# EPROM-EMU.net
KiCad netlist of a schematic drawn in Altium Designer
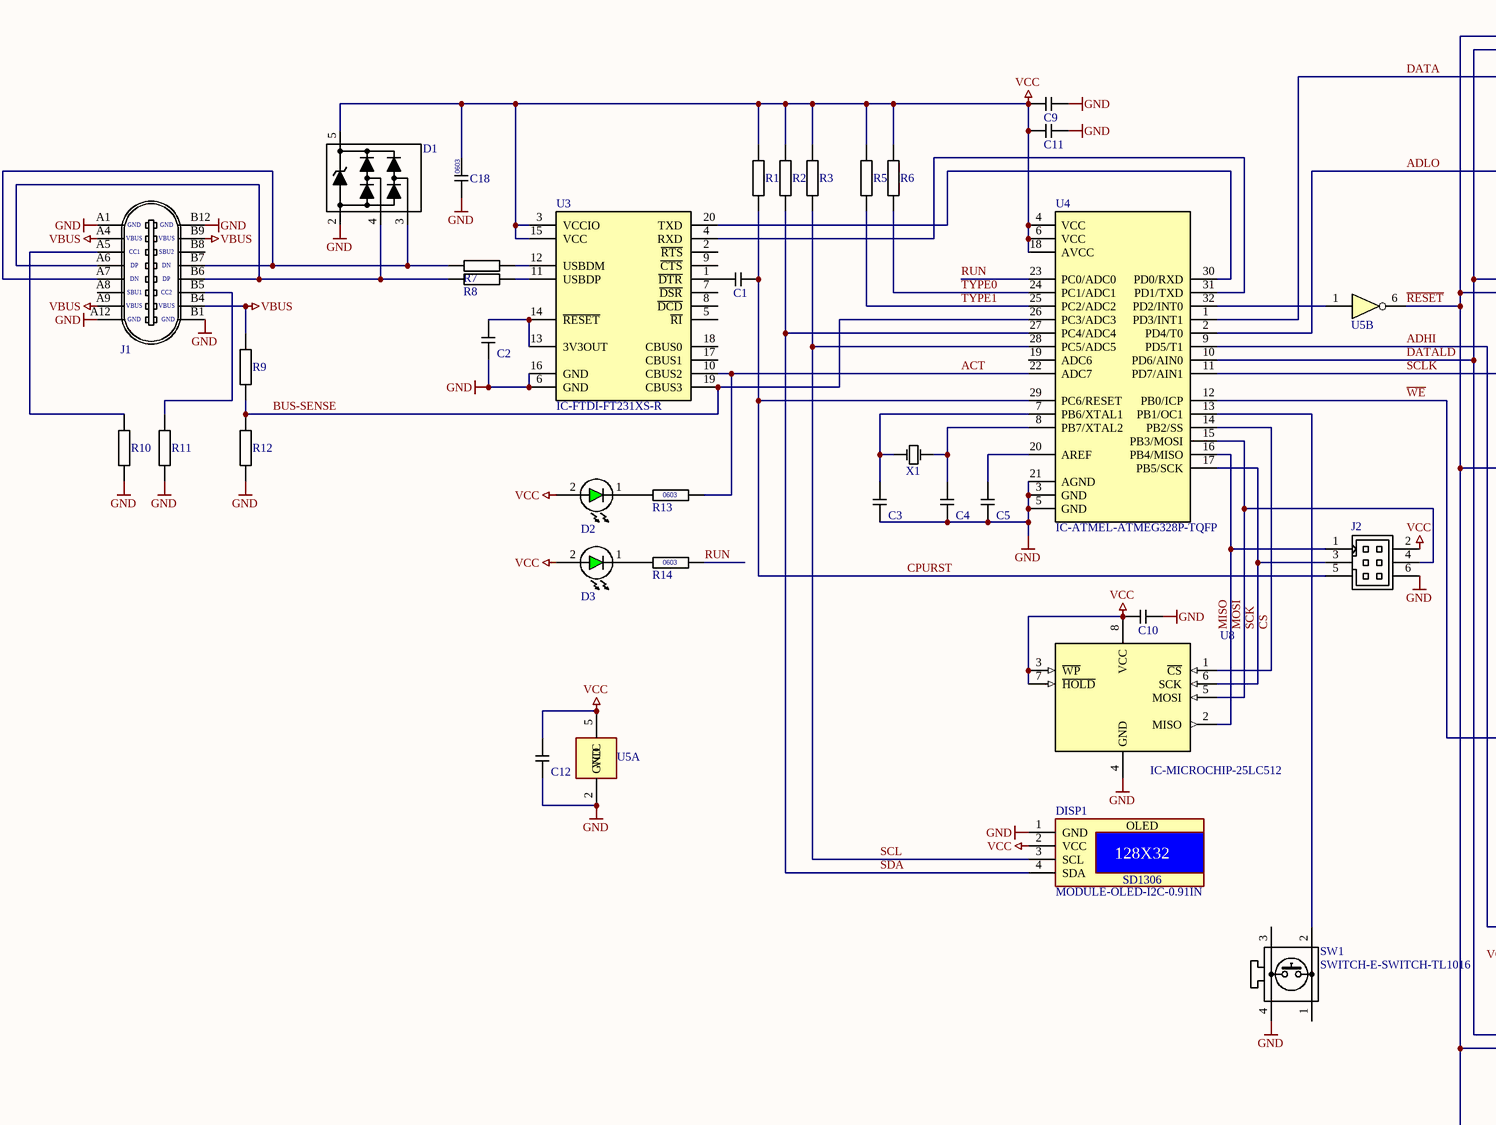
[diagram p0: EPROM-EMU.SchDoc, left]
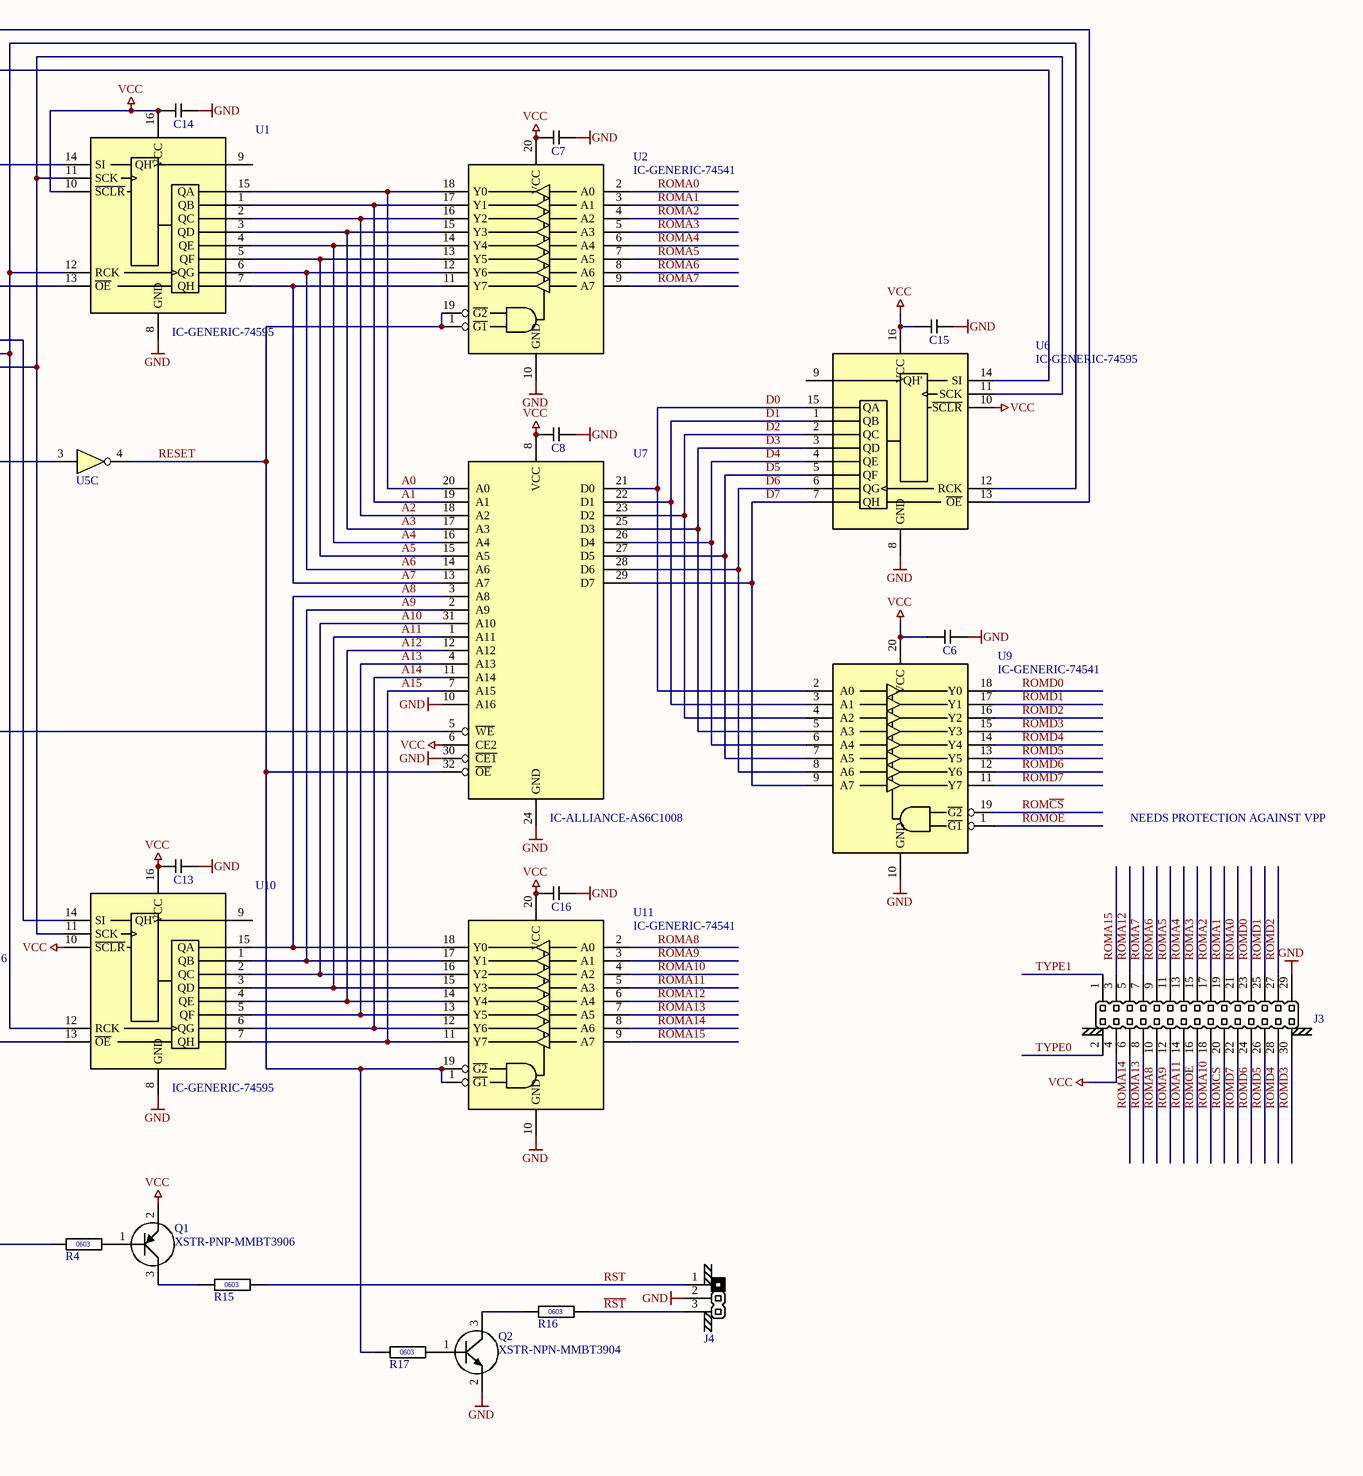
[diagram p1: EPROM-EMU.SchDoc, right]

(export (version "E")
  (design (tool "Eeschema 10.0.6"))
  (components
    (comp (ref "C1")
      (value "GENERIC-CAP")
      (footprint "CAP0603")
      (libsource (lib "eprom-emu") (part "GENERIC-CAP"))
    )
    (comp (ref "C2")
      (value "GENERIC-CAP")
      (footprint "CAP0603")
      (libsource (lib "eprom-emu") (part "GENERIC-CAP"))
    )
    (comp (ref "C3")
      (value "GENERIC-CAP")
      (footprint "CAP0603")
      (libsource (lib "eprom-emu") (part "GENERIC-CAP"))
    )
    (comp (ref "C4")
      (value "GENERIC-CAP")
      (footprint "CAP0603")
      (libsource (lib "eprom-emu") (part "GENERIC-CAP"))
    )
    (comp (ref "C5")
      (value "GENERIC-CAP")
      (footprint "CAP0603")
      (libsource (lib "eprom-emu") (part "GENERIC-CAP"))
    )
    (comp (ref "C6")
      (value "GENERIC-CAP")
      (footprint "CAP0603")
      (libsource (lib "eprom-emu") (part "GENERIC-CAP"))
    )
    (comp (ref "C7")
      (value "GENERIC-CAP")
      (footprint "CAP0603")
      (libsource (lib "eprom-emu") (part "GENERIC-CAP"))
    )
    (comp (ref "C8")
      (value "GENERIC-CAP")
      (footprint "CAP0603")
      (libsource (lib "eprom-emu") (part "GENERIC-CAP"))
    )
    (comp (ref "C9")
      (value "GENERIC-CAP")
      (footprint "CAP0603")
      (libsource (lib "eprom-emu") (part "GENERIC-CAP"))
    )
    (comp (ref "C10")
      (value "GENERIC-CAP")
      (footprint "CAP0603")
      (libsource (lib "eprom-emu") (part "GENERIC-CAP"))
    )
    (comp (ref "C11")
      (value "GENERIC-CAP")
      (footprint "CAP0603")
      (libsource (lib "eprom-emu") (part "GENERIC-CAP"))
    )
    (comp (ref "C12")
      (value "GENERIC-CAP")
      (footprint "CAP0603")
      (libsource (lib "eprom-emu") (part "GENERIC-CAP"))
    )
    (comp (ref "C13")
      (value "GENERIC-CAP")
      (footprint "CAP0603")
      (libsource (lib "eprom-emu") (part "GENERIC-CAP"))
    )
    (comp (ref "C14")
      (value "GENERIC-CAP")
      (footprint "CAP0603")
      (libsource (lib "eprom-emu") (part "GENERIC-CAP"))
    )
    (comp (ref "C15")
      (value "GENERIC-CAP")
      (footprint "CAP0603")
      (libsource (lib "eprom-emu") (part "GENERIC-CAP"))
    )
    (comp (ref "C16")
      (value "GENERIC-CAP")
      (footprint "CAP0603")
      (libsource (lib "eprom-emu") (part "GENERIC-CAP"))
    )
    (comp (ref "C18")
      (value "GENERIC-CAP-0603")
      (footprint "CAP0603")
      (libsource (lib "eprom-emu") (part "GENERIC-CAP-0603"))
    )
    (comp (ref "D1")
      (value "TVS-WURTH-824011")
      (footprint "SOT23-5")
      (libsource (lib "eprom-emu") (part "TVS-WURTH-824011"))
    )
    (comp (ref "D2")
      (value "LED-PLCC2-GREEN")
      (footprint "LED-PLCC2-GREEN")
      (libsource (lib "eprom-emu") (part "LED-PLCC2-GREEN"))
    )
    (comp (ref "D3")
      (value "LED-PLCC2-GREEN")
      (footprint "LED-PLCC2-GREEN")
      (libsource (lib "eprom-emu") (part "LED-PLCC2-GREEN"))
    )
    (comp (ref "DISP1")
      (value "MODULE-OLED-I2C-0.91IN")
      (footprint "DISP-OLED-128X32")
      (libsource (lib "eprom-emu") (part "MODULE-OLED-I2C-0.91IN"))
    )
    (comp (ref "J1")
      (value "CUNN-USBC-USB2-VERT")
      (footprint "CONN-GCT-USB4085")
      (libsource (lib "eprom-emu") (part "CUNN-USBC-USB2-VERT"))
    )
    (comp (ref "J2")
      (value "BOXHEADER-3X2")
      (footprint "HEADER-2X3-1.27")
      (libsource (lib "eprom-emu") (part "CONN-BOXHEADER-3X2"))
    )
    (comp (ref "J3")
      (value "CONN-HEADER-RA-PIN-15X2")
      (footprint "HEADER-2X15-RA")
      (libsource (lib "eprom-emu") (part "CONN-HEADER-RA-PIN-15X2"))
    )
    (comp (ref "J4")
      (value "CONN-HEADER-PIN-1X3-254-RA")
      (footprint "HEADER-1X3-245-RA")
      (libsource (lib "eprom-emu") (part "CONN-HEADER-PIN-1X3-254-RA"))
    )
    (comp (ref "Q1")
      (value "XSTR-PNP-MMBT3906")
      (footprint "SOT23")
      (libsource (lib "eprom-emu") (part "XSTR-PNP-MMBT3906"))
    )
    (comp (ref "Q2")
      (value "XSTR-NPN-MMBT3904")
      (footprint "SOT23")
      (libsource (lib "eprom-emu") (part "XSTR-NPN-MMBT3904"))
    )
    (comp (ref "R1")
      (value "GENERIC-RES")
      (footprint "RES0603")
      (libsource (lib "eprom-emu") (part "GENERIC-RES"))
    )
    (comp (ref "R2")
      (value "GENERIC-RES")
      (footprint "RES0603")
      (libsource (lib "eprom-emu") (part "GENERIC-RES"))
    )
    (comp (ref "R3")
      (value "GENERIC-RES")
      (footprint "RES0603")
      (libsource (lib "eprom-emu") (part "GENERIC-RES"))
    )
    (comp (ref "R4")
      (value "GENERIC-RES-0603")
      (footprint "RES0603")
      (libsource (lib "eprom-emu") (part "GENERIC-RES-0603"))
    )
    (comp (ref "R5")
      (value "GENERIC-RES")
      (footprint "RES0603")
      (libsource (lib "eprom-emu") (part "GENERIC-RES"))
    )
    (comp (ref "R6")
      (value "GENERIC-RES")
      (footprint "RES0603")
      (libsource (lib "eprom-emu") (part "GENERIC-RES"))
    )
    (comp (ref "R7")
      (value "GENERIC-RES")
      (footprint "RES0603")
      (libsource (lib "eprom-emu") (part "GENERIC-RES"))
    )
    (comp (ref "R8")
      (value "GENERIC-RES")
      (footprint "RES0603")
      (libsource (lib "eprom-emu") (part "GENERIC-RES"))
    )
    (comp (ref "R9")
      (value "GENERIC-RES")
      (footprint "RES0603")
      (libsource (lib "eprom-emu") (part "GENERIC-RES"))
    )
    (comp (ref "R10")
      (value "GENERIC-RES")
      (footprint "RES0603")
      (libsource (lib "eprom-emu") (part "GENERIC-RES"))
    )
    (comp (ref "R11")
      (value "GENERIC-RES")
      (footprint "RES0603")
      (libsource (lib "eprom-emu") (part "GENERIC-RES"))
    )
    (comp (ref "R12")
      (value "GENERIC-RES")
      (footprint "RES0603")
      (libsource (lib "eprom-emu") (part "GENERIC-RES"))
    )
    (comp (ref "R13")
      (value "GENERIC-RES-0603")
      (footprint "RES0603")
      (libsource (lib "eprom-emu") (part "GENERIC-RES-0603"))
    )
    (comp (ref "R14")
      (value "GENERIC-RES-0603")
      (footprint "RES0603")
      (libsource (lib "eprom-emu") (part "GENERIC-RES-0603"))
    )
    (comp (ref "R15")
      (value "GENERIC-RES-0603")
      (footprint "RES0603")
      (libsource (lib "eprom-emu") (part "GENERIC-RES-0603"))
    )
    (comp (ref "R16")
      (value "GENERIC-RES-0603")
      (footprint "RES0603")
      (libsource (lib "eprom-emu") (part "GENERIC-RES-0603"))
    )
    (comp (ref "R17")
      (value "GENERIC-RES-0603")
      (footprint "RES0603")
      (libsource (lib "eprom-emu") (part "GENERIC-RES-0603"))
    )
    (comp (ref "SW1")
      (value "SWITCH-E-SWITCH-TL1016")
      (footprint "SWITCH-ESWITCH-TL1016")
      (libsource (lib "eprom-emu") (part "SWITCH-E-SWITCH-TL1016"))
    )
    (comp (ref "U1")
      (value "IC-GENERIC-74595")
      (footprint "SO65P640X120-16N")
      (libsource (lib "eprom-emu") (part "IC-GENERIC-74595"))
    )
    (comp (ref "U2")
      (value "IC-GENERIC-74541")
      (footprint "SO65P640X110-20N")
      (libsource (lib "eprom-emu") (part "IC-GENERIC-74541"))
    )
    (comp (ref "U3")
      (value "IC-FTDI-FT231XS-R")
      (footprint "TSOP65P640-20N")
      (libsource (lib "eprom-emu") (part "IC-FTDI-FT231XS-R"))
    )
    (comp (ref "U4")
      (value "IC-ATMEL-ATMEG328P-TQFP")
      (footprint "QFP80P900X900-32N")
      (libsource (lib "eprom-emu") (part "IC-ATMEL-ATMEG328P-TQFP"))
    )
    (comp (ref "U5")
      (value "IC-TI-SN74LVC2G14")
      (footprint "SOT23-6")
      (description "IC-GENERIC-7408IC-TI-SN74LVC2G14")
      (libsource (lib "eprom-emu") (part "IC-TI-SN74LVC2G14"))
    )
    (comp (ref "U6")
      (value "IC-GENERIC-74595")
      (footprint "SO65P640X120-16N")
      (libsource (lib "") (part "IC-GENERIC-74595_1"))
    )
    (comp (ref "U7")
      (value "IC-ALLIANCE-AS6C1008")
      (footprint "TSSOP50P1340X125-32N")
      (libsource (lib "eprom-emu") (part "IC-ALLIANCE-AS6C1008"))
    )
    (comp (ref "U8")
      (value "IC-MICROCHIP-25LC512")
      (footprint "SO127P600-8N")
      (libsource (lib "eprom-emu") (part "IC-MICROCHIP-25LC512"))
    )
    (comp (ref "U9")
      (value "IC-GENERIC-74541")
      (footprint "SO65P640X110-20N")
      (libsource (lib "") (part "IC-GENERIC-74541_1"))
    )
    (comp (ref "U10")
      (value "IC-GENERIC-74595")
      (footprint "SO65P640X120-16N")
      (libsource (lib "eprom-emu") (part "IC-GENERIC-74595"))
    )
    (comp (ref "U11")
      (value "IC-GENERIC-74541")
      (footprint "SO65P640X110-20N")
      (libsource (lib "eprom-emu") (part "IC-GENERIC-74541"))
    )
    (comp (ref "X1")
      (value "CRYSTAL-2PIN")
      (footprint "XTAL-ABRACON-ABM3")
      (description "CRYSTAL 2 PIN GENERIC")
      (libsource (lib "eprom-emu") (part "CRYSTAL-2PIN"))
    )
  )
  (nets
    (net (code "1") (name "/A0") (class "Default")
      (node (ref "U1") (pin "15") (pinfunction "QA_15") (pintype "power_in"))
      (node (ref "U2") (pin "18") (pinfunction "Y0_18") (pintype "power_in"))
      (node (ref "U7") (pin "20") (pinfunction "A0_20") (pintype "passive"))
    )
    (net (code "2") (name "/A1") (class "Default")
      (node (ref "U1") (pin "1") (pinfunction "QB_1") (pintype "power_in"))
      (node (ref "U2") (pin "17") (pinfunction "Y1_17") (pintype "power_in"))
      (node (ref "U7") (pin "19") (pinfunction "A1_19") (pintype "passive"))
    )
    (net (code "3") (name "/A2") (class "Default")
      (node (ref "U1") (pin "2") (pinfunction "QC_2") (pintype "power_in"))
      (node (ref "U2") (pin "16") (pinfunction "Y2_16") (pintype "power_in"))
      (node (ref "U7") (pin "18") (pinfunction "A2_18") (pintype "passive"))
    )
    (net (code "4") (name "/A3") (class "Default")
      (node (ref "U1") (pin "3") (pinfunction "QD_3") (pintype "power_in"))
      (node (ref "U2") (pin "15") (pinfunction "Y3_15") (pintype "power_in"))
      (node (ref "U7") (pin "17") (pinfunction "A3_17") (pintype "passive"))
    )
    (net (code "5") (name "/A4") (class "Default")
      (node (ref "U1") (pin "4") (pinfunction "QE_4") (pintype "power_in"))
      (node (ref "U2") (pin "14") (pinfunction "Y4_14") (pintype "power_in"))
      (node (ref "U7") (pin "16") (pinfunction "A4_16") (pintype "passive"))
    )
    (net (code "6") (name "/A5") (class "Default")
      (node (ref "U1") (pin "5") (pinfunction "QF_5") (pintype "power_in"))
      (node (ref "U2") (pin "13") (pinfunction "Y5_13") (pintype "power_in"))
      (node (ref "U7") (pin "15") (pinfunction "A5_15") (pintype "passive"))
    )
    (net (code "7") (name "/A6") (class "Default")
      (node (ref "U1") (pin "6") (pinfunction "QG_6") (pintype "power_in"))
      (node (ref "U2") (pin "12") (pinfunction "Y6_12") (pintype "power_in"))
      (node (ref "U7") (pin "14") (pinfunction "A6_14") (pintype "passive"))
    )
    (net (code "8") (name "/A7") (class "Default")
      (node (ref "U1") (pin "7") (pinfunction "QH_7") (pintype "power_in"))
      (node (ref "U2") (pin "11") (pinfunction "Y7_11") (pintype "power_in"))
      (node (ref "U7") (pin "13") (pinfunction "A7_13") (pintype "passive"))
    )
    (net (code "9") (name "/A8") (class "Default")
      (node (ref "U10") (pin "15") (pinfunction "QA_15") (pintype "power_in"))
      (node (ref "U11") (pin "18") (pinfunction "Y0_18") (pintype "power_in"))
      (node (ref "U7") (pin "3") (pinfunction "A8_3") (pintype "passive"))
    )
    (net (code "10") (name "/A9") (class "Default")
      (node (ref "U10") (pin "1") (pinfunction "QB_1") (pintype "power_in"))
      (node (ref "U11") (pin "17") (pinfunction "Y1_17") (pintype "power_in"))
      (node (ref "U7") (pin "2") (pinfunction "A9_2") (pintype "passive"))
    )
    (net (code "11") (name "/A10") (class "Default")
      (node (ref "U10") (pin "2") (pinfunction "QC_2") (pintype "power_in"))
      (node (ref "U11") (pin "16") (pinfunction "Y2_16") (pintype "power_in"))
      (node (ref "U7") (pin "31") (pinfunction "A10_31") (pintype "passive"))
    )
    (net (code "12") (name "/A11") (class "Default")
      (node (ref "U10") (pin "3") (pinfunction "QD_3") (pintype "power_in"))
      (node (ref "U11") (pin "15") (pinfunction "Y3_15") (pintype "power_in"))
      (node (ref "U7") (pin "1") (pinfunction "A11_1") (pintype "passive"))
    )
    (net (code "13") (name "/A12") (class "Default")
      (node (ref "U10") (pin "4") (pinfunction "QE_4") (pintype "power_in"))
      (node (ref "U11") (pin "14") (pinfunction "Y4_14") (pintype "power_in"))
      (node (ref "U7") (pin "12") (pinfunction "A12_12") (pintype "passive"))
    )
    (net (code "14") (name "/A13") (class "Default")
      (node (ref "U10") (pin "5") (pinfunction "QF_5") (pintype "power_in"))
      (node (ref "U11") (pin "13") (pinfunction "Y5_13") (pintype "power_in"))
      (node (ref "U7") (pin "4") (pinfunction "A13_4") (pintype "passive"))
    )
    (net (code "15") (name "/A14") (class "Default")
      (node (ref "U10") (pin "6") (pinfunction "QG_6") (pintype "power_in"))
      (node (ref "U11") (pin "12") (pinfunction "Y6_12") (pintype "power_in"))
      (node (ref "U7") (pin "11") (pinfunction "A14_11") (pintype "passive"))
    )
    (net (code "16") (name "/A15") (class "Default")
      (node (ref "U10") (pin "7") (pinfunction "QH_7") (pintype "power_in"))
      (node (ref "U11") (pin "11") (pinfunction "Y7_11") (pintype "power_in"))
      (node (ref "U7") (pin "7") (pinfunction "A15_7") (pintype "passive"))
    )
    (net (code "17") (name "/ACT") (class "Default")
      (node (ref "R13") (pin "1") (pinfunction "1_1") (pintype "passive"))
      (node (ref "U3") (pin "10") (pinfunction "CBUS2_10") (pintype "power_in"))
      (node (ref "U4") (pin "22") (pinfunction "ADC7_22") (pintype "passive"))
    )
    (net (code "18") (name "/ADHI") (class "Default")
      (node (ref "U10") (pin "14") (pinfunction "SI_14") (pintype "power_in"))
      (node (ref "U4") (pin "9") (pinfunction "PD5/T1_9") (pintype "passive"))
    )
    (net (code "19") (name "/ADLO") (class "Default")
      (node (ref "U1") (pin "14") (pinfunction "SI_14") (pintype "power_in"))
      (node (ref "U4") (pin "2") (pinfunction "PD4/T0_2") (pintype "passive"))
    )
    (net (code "20") (name "/BUS-SENSE") (class "Default")
      (node (ref "R12") (pin "1") (pinfunction "1_1") (pintype "passive"))
      (node (ref "R9") (pin "2") (pinfunction "2_2") (pintype "passive"))
      (node (ref "U3") (pin "19") (pinfunction "CBUS3_19") (pintype "power_in"))
      (node (ref "U4") (pin "26") (pinfunction "PC3/ADC3_26") (pintype "passive"))
    )
    (net (code "21") (name "/CPURST") (class "Default")
      (node (ref "C1") (pin "2") (pinfunction "2_2") (pintype "passive"))
      (node (ref "J2") (pin "5") (pinfunction "-_5") (pintype "passive"))
      (node (ref "R1") (pin "1") (pinfunction "1_1") (pintype "passive"))
      (node (ref "U4") (pin "29") (pinfunction "PC6/RESET_29") (pintype "passive"))
    )
    (net (code "22") (name "/D0") (class "Default")
      (node (ref "U6") (pin "15") (pinfunction "QA_15") (pintype "power_in"))
      (node (ref "U7") (pin "21") (pinfunction "D0_21") (pintype "power_in"))
      (node (ref "U9") (pin "2") (pinfunction "A0_2") (pintype "power_in"))
    )
    (net (code "23") (name "/D1") (class "Default")
      (node (ref "U6") (pin "1") (pinfunction "QB_1") (pintype "power_in"))
      (node (ref "U7") (pin "22") (pinfunction "D1_22") (pintype "power_in"))
      (node (ref "U9") (pin "3") (pinfunction "A1_3") (pintype "power_in"))
    )
    (net (code "24") (name "/D2") (class "Default")
      (node (ref "U6") (pin "2") (pinfunction "QC_2") (pintype "power_in"))
      (node (ref "U7") (pin "23") (pinfunction "D2_23") (pintype "power_in"))
      (node (ref "U9") (pin "4") (pinfunction "A2_4") (pintype "power_in"))
    )
    (net (code "25") (name "/D3") (class "Default")
      (node (ref "U6") (pin "3") (pinfunction "QD_3") (pintype "power_in"))
      (node (ref "U7") (pin "25") (pinfunction "D3_25") (pintype "power_in"))
      (node (ref "U9") (pin "5") (pinfunction "A3_5") (pintype "power_in"))
    )
    (net (code "26") (name "/D4") (class "Default")
      (node (ref "U6") (pin "4") (pinfunction "QE_4") (pintype "power_in"))
      (node (ref "U7") (pin "26") (pinfunction "D4_26") (pintype "power_in"))
      (node (ref "U9") (pin "6") (pinfunction "A4_6") (pintype "power_in"))
    )
    (net (code "27") (name "/D5") (class "Default")
      (node (ref "U6") (pin "5") (pinfunction "QF_5") (pintype "power_in"))
      (node (ref "U7") (pin "27") (pinfunction "D5_27") (pintype "power_in"))
      (node (ref "U9") (pin "7") (pinfunction "A5_7") (pintype "power_in"))
    )
    (net (code "28") (name "/D6") (class "Default")
      (node (ref "U6") (pin "6") (pinfunction "QG_6") (pintype "power_in"))
      (node (ref "U7") (pin "28") (pinfunction "D6_28") (pintype "power_in"))
      (node (ref "U9") (pin "8") (pinfunction "A6_8") (pintype "power_in"))
    )
    (net (code "29") (name "/D7") (class "Default")
      (node (ref "U6") (pin "7") (pinfunction "QH_7") (pintype "power_in"))
      (node (ref "U7") (pin "29") (pinfunction "D7_29") (pintype "power_in"))
      (node (ref "U9") (pin "9") (pinfunction "A7_9") (pintype "power_in"))
    )
    (net (code "30") (name "/DATA") (class "Default")
      (node (ref "U4") (pin "1") (pinfunction "PD3/INT1_1") (pintype "passive"))
      (node (ref "U6") (pin "14") (pinfunction "SI_14") (pintype "power_in"))
    )
    (net (code "31") (name "/DATALD") (class "Default")
      (node (ref "U1") (pin "12") (pinfunction "RCK_12") (pintype "power_in"))
      (node (ref "U10") (pin "12") (pinfunction "RCK_12") (pintype "power_in"))
      (node (ref "U4") (pin "10") (pinfunction "PD6/AIN0_10") (pintype "passive"))
      (node (ref "U6") (pin "12") (pinfunction "RCK_12") (pintype "power_in"))
    )
    (net (code "32") (name "/MISO") (class "Default")
      (node (ref "J2") (pin "1") (pinfunction "+_1") (pintype "passive"))
      (node (ref "U4") (pin "16") (pinfunction "PB4/MISO_16") (pintype "passive"))
      (node (ref "U8") (pin "2") (pinfunction "MISO_2") (pintype "output"))
    )
    (net (code "33") (name "/MOSI") (class "Default")
      (node (ref "J2") (pin "4") (pinfunction "-_4") (pintype "passive"))
      (node (ref "U4") (pin "15") (pinfunction "PB3/MOSI_15") (pintype "passive"))
      (node (ref "U8") (pin "5") (pinfunction "MOSI_5") (pintype "input"))
    )
    (net (code "34") (name "/RESET") (class "Default")
      (node (ref "R17") (pin "2") (pinfunction "2_2") (pintype "passive"))
      (node (ref "U11") (pin "1") (pinfunction "~{G1}_1") (pintype "power_in"))
      (node (ref "U11") (pin "19") (pinfunction "~{G2}_19") (pintype "power_in"))
      (node (ref "U2") (pin "1") (pinfunction "~{G1}_1") (pintype "power_in"))
      (node (ref "U2") (pin "19") (pinfunction "~{G2}_19") (pintype "power_in"))
      (node (ref "U5") (pin "4") (pinfunction "4_4") (pintype "passive"))
      (node (ref "U7") (pin "32") (pinfunction "~{OE}_32") (pintype "power_in"))
    )
    (net (code "35") (name "/ROMA0") (class "Default")
      (node (ref "J3") (pin "21") (pinfunction "-_21") (pintype "passive"))
      (node (ref "U2") (pin "2") (pinfunction "A0_2") (pintype "power_in"))
    )
    (net (code "36") (name "/ROMA1") (class "Default")
      (node (ref "J3") (pin "19") (pinfunction "+_19") (pintype "passive"))
      (node (ref "U2") (pin "3") (pinfunction "A1_3") (pintype "power_in"))
    )
    (net (code "37") (name "/ROMA2") (class "Default")
      (node (ref "J3") (pin "17") (pinfunction "-_17") (pintype "passive"))
      (node (ref "U2") (pin "4") (pinfunction "A2_4") (pintype "power_in"))
    )
    (net (code "38") (name "/ROMA3") (class "Default")
      (node (ref "J3") (pin "15") (pinfunction "-_15") (pintype "passive"))
      (node (ref "U2") (pin "5") (pinfunction "A3_5") (pintype "power_in"))
    )
    (net (code "39") (name "/ROMA4") (class "Default")
      (node (ref "J3") (pin "13") (pinfunction "+_13") (pintype "passive"))
      (node (ref "U2") (pin "6") (pinfunction "A4_6") (pintype "power_in"))
    )
    (net (code "40") (name "/ROMA5") (class "Default")
      (node (ref "J3") (pin "11") (pinfunction "-_11") (pintype "passive"))
      (node (ref "U2") (pin "7") (pinfunction "A5_7") (pintype "power_in"))
    )
    (net (code "41") (name "/ROMA6") (class "Default")
      (node (ref "J3") (pin "9") (pinfunction "-_9") (pintype "passive"))
      (node (ref "U2") (pin "8") (pinfunction "A6_8") (pintype "power_in"))
    )
    (net (code "42") (name "/ROMA7") (class "Default")
      (node (ref "J3") (pin "7") (pinfunction "+_7") (pintype "passive"))
      (node (ref "U2") (pin "9") (pinfunction "A7_9") (pintype "power_in"))
    )
    (net (code "43") (name "/ROMA8") (class "Default")
      (node (ref "J3") (pin "10") (pinfunction "-_10") (pintype "passive"))
      (node (ref "U11") (pin "2") (pinfunction "A0_2") (pintype "power_in"))
    )
    (net (code "44") (name "/ROMA9") (class "Default")
      (node (ref "J3") (pin "12") (pinfunction "-_12") (pintype "passive"))
      (node (ref "U11") (pin "3") (pinfunction "A1_3") (pintype "power_in"))
    )
    (net (code "45") (name "/ROMA10") (class "Default")
      (node (ref "J3") (pin "18") (pinfunction "-_18") (pintype "passive"))
      (node (ref "U11") (pin "4") (pinfunction "A2_4") (pintype "power_in"))
    )
    (net (code "46") (name "/ROMA11") (class "Default")
      (node (ref "J3") (pin "14") (pinfunction "-_14") (pintype "passive"))
      (node (ref "U11") (pin "5") (pinfunction "A3_5") (pintype "power_in"))
    )
    (net (code "47") (name "/ROMA12") (class "Default")
      (node (ref "J3") (pin "5") (pinfunction "-_5") (pintype "passive"))
      (node (ref "U11") (pin "6") (pinfunction "A4_6") (pintype "power_in"))
    )
    (net (code "48") (name "/ROMA13") (class "Default")
      (node (ref "J3") (pin "8") (pinfunction "-_8") (pintype "passive"))
      (node (ref "U11") (pin "7") (pinfunction "A5_7") (pintype "power_in"))
    )
    (net (code "49") (name "/ROMA14") (class "Default")
      (node (ref "J3") (pin "6") (pinfunction "-_6") (pintype "passive"))
      (node (ref "U11") (pin "8") (pinfunction "A6_8") (pintype "power_in"))
    )
    (net (code "50") (name "/ROMA15") (class "Default")
      (node (ref "J3") (pin "3") (pinfunction "-_3") (pintype "passive"))
      (node (ref "U11") (pin "9") (pinfunction "A7_9") (pintype "power_in"))
    )
    (net (code "51") (name "/ROMD0") (class "Default")
      (node (ref "J3") (pin "23") (pinfunction "-_23") (pintype "passive"))
      (node (ref "U9") (pin "18") (pinfunction "Y0_18") (pintype "power_in"))
    )
    (net (code "52") (name "/ROMD1") (class "Default")
      (node (ref "J3") (pin "25") (pinfunction "+_25") (pintype "passive"))
      (node (ref "U9") (pin "17") (pinfunction "Y1_17") (pintype "power_in"))
    )
    (net (code "53") (name "/ROMD2") (class "Default")
      (node (ref "J3") (pin "27") (pinfunction "-_27") (pintype "passive"))
      (node (ref "U9") (pin "16") (pinfunction "Y2_16") (pintype "power_in"))
    )
    (net (code "54") (name "/ROMD3") (class "Default")
      (node (ref "J3") (pin "30") (pinfunction "-_30") (pintype "passive"))
      (node (ref "U9") (pin "15") (pinfunction "Y3_15") (pintype "power_in"))
    )
    (net (code "55") (name "/ROMD4") (class "Default")
      (node (ref "J3") (pin "28") (pinfunction "-_28") (pintype "passive"))
      (node (ref "U9") (pin "14") (pinfunction "Y4_14") (pintype "power_in"))
    )
    (net (code "56") (name "/ROMD5") (class "Default")
      (node (ref "J3") (pin "26") (pinfunction "-_26") (pintype "passive"))
      (node (ref "U9") (pin "13") (pinfunction "Y5_13") (pintype "power_in"))
    )
    (net (code "57") (name "/ROMD6") (class "Default")
      (node (ref "J3") (pin "24") (pinfunction "-_24") (pintype "passive"))
      (node (ref "U9") (pin "12") (pinfunction "Y6_12") (pintype "power_in"))
    )
    (net (code "58") (name "/ROMD7") (class "Default")
      (node (ref "J3") (pin "22") (pinfunction "-_22") (pintype "passive"))
      (node (ref "U9") (pin "11") (pinfunction "Y7_11") (pintype "power_in"))
    )
    (net (code "59") (name "/ROM~{CS}") (class "Default")
      (node (ref "J3") (pin "20") (pinfunction "-_20") (pintype "passive"))
      (node (ref "U9") (pin "19") (pinfunction "~{G2}_19") (pintype "power_in"))
    )
    (net (code "60") (name "/ROM~{OE}") (class "Default")
      (node (ref "J3") (pin "16") (pinfunction "-_16") (pintype "passive"))
      (node (ref "U9") (pin "1") (pinfunction "~{G1}_1") (pintype "power_in"))
    )
    (net (code "61") (name "/RST") (class "Default")
      (node (ref "J4") (pin "1") (pinfunction "+_1") (pintype "passive"))
      (node (ref "R15") (pin "1") (pinfunction "1_1") (pintype "passive"))
    )
    (net (code "62") (name "/RUN") (class "Default")
      (node (ref "R14") (pin "1") (pinfunction "1_1") (pintype "passive"))
      (node (ref "U4") (pin "23") (pinfunction "PC0/ADC0_23") (pintype "passive"))
    )
    (net (code "63") (name "/SCK") (class "Default")
      (node (ref "J2") (pin "3") (pinfunction "-_3") (pintype "passive"))
      (node (ref "U4") (pin "17") (pinfunction "PB5/SCK_17") (pintype "passive"))
      (node (ref "U8") (pin "6") (pinfunction "SCK_6") (pintype "input"))
    )
    (net (code "64") (name "/SCL") (class "Default")
      (node (ref "DISP1") (pin "3") (pinfunction "SCL_3") (pintype "passive"))
      (node (ref "R3") (pin "1") (pinfunction "1_1") (pintype "passive"))
      (node (ref "U4") (pin "28") (pinfunction "PC5/ADC5_28") (pintype "passive"))
    )
    (net (code "65") (name "/SCLK") (class "Default")
      (node (ref "U1") (pin "11") (pinfunction "SCK_11") (pintype "power_in"))
      (node (ref "U10") (pin "11") (pinfunction "SCK_11") (pintype "power_in"))
      (node (ref "U4") (pin "11") (pinfunction "PD7/AIN1_11") (pintype "passive"))
      (node (ref "U6") (pin "11") (pinfunction "SCK_11") (pintype "power_in"))
    )
    (net (code "66") (name "/SDA") (class "Default")
      (node (ref "DISP1") (pin "4") (pinfunction "SDA_4") (pintype "passive"))
      (node (ref "R2") (pin "1") (pinfunction "1_1") (pintype "passive"))
      (node (ref "U4") (pin "27") (pinfunction "PC4/ADC4_27") (pintype "passive"))
    )
    (net (code "67") (name "/TYPE0") (class "Default")
      (node (ref "J3") (pin "2") (pinfunction "-_2") (pintype "passive"))
      (node (ref "R6") (pin "1") (pinfunction "1_1") (pintype "passive"))
      (node (ref "U4") (pin "24") (pinfunction "PC1/ADC1_24") (pintype "passive"))
    )
    (net (code "68") (name "/TYPE1") (class "Default")
      (node (ref "J3") (pin "1") (pinfunction "+_1") (pintype "passive"))
      (node (ref "R5") (pin "1") (pinfunction "1_1") (pintype "passive"))
      (node (ref "U4") (pin "25") (pinfunction "PC2/ADC2_25") (pintype "passive"))
    )
    (net (code "69") (name "/~{CS}") (class "Default")
      (node (ref "U4") (pin "14") (pinfunction "PB2/SS_14") (pintype "passive"))
      (node (ref "U8") (pin "1") (pinfunction "~{CS}_1") (pintype "input"))
    )
    (net (code "70") (name "/~{RESET}") (class "Default")
      (node (ref "R4") (pin "2") (pinfunction "2_2") (pintype "passive"))
      (node (ref "U1") (pin "13") (pinfunction "~{OE}_13") (pintype "power_in"))
      (node (ref "U10") (pin "13") (pinfunction "~{OE}_13") (pintype "power_in"))
      (node (ref "U5") (pin "3") (pinfunction "3_3") (pintype "passive"))
      (node (ref "U5") (pin "6") (pinfunction "6_6") (pintype "passive"))
      (node (ref "U6") (pin "13") (pinfunction "~{OE}_13") (pintype "power_in"))
    )
    (net (code "71") (name "/~{RST}") (class "Default")
      (node (ref "J4") (pin "3") (pinfunction "+_3") (pintype "passive"))
      (node (ref "R16") (pin "1") (pinfunction "1_1") (pintype "passive"))
    )
    (net (code "72") (name "/~{WE}") (class "Default")
      (node (ref "U4") (pin "12") (pinfunction "PB0/ICP_12") (pintype "passive"))
      (node (ref "U7") (pin "5") (pinfunction "~{WE}_5") (pintype "power_in"))
    )
    (net (code "73") (name "GND") (class "Default")
      (node (ref "C10") (pin "2") (pinfunction "2_2") (pintype "passive"))
      (node (ref "C11") (pin "2") (pinfunction "2_2") (pintype "passive"))
      (node (ref "C12") (pin "2") (pinfunction "2_2") (pintype "passive"))
      (node (ref "C13") (pin "2") (pinfunction "2_2") (pintype "passive"))
      (node (ref "C14") (pin "2") (pinfunction "2_2") (pintype "passive"))
      (node (ref "C15") (pin "2") (pinfunction "2_2") (pintype "passive"))
      (node (ref "C16") (pin "2") (pinfunction "2_2") (pintype "passive"))
      (node (ref "C18") (pin "2") (pinfunction "2_2") (pintype "passive"))
      (node (ref "C2") (pin "2") (pinfunction "2_2") (pintype "passive"))
      (node (ref "C3") (pin "2") (pinfunction "2_2") (pintype "passive"))
      (node (ref "C4") (pin "2") (pinfunction "2_2") (pintype "passive"))
      (node (ref "C5") (pin "2") (pinfunction "2_2") (pintype "passive"))
      (node (ref "C6") (pin "2") (pinfunction "2_2") (pintype "passive"))
      (node (ref "C7") (pin "2") (pinfunction "2_2") (pintype "passive"))
      (node (ref "C8") (pin "2") (pinfunction "2_2") (pintype "passive"))
      (node (ref "C9") (pin "2") (pinfunction "2_2") (pintype "passive"))
      (node (ref "D1") (pin "2") (pinfunction "A_2") (pintype "passive"))
      (node (ref "DISP1") (pin "1") (pinfunction "GND_1") (pintype "passive"))
      (node (ref "J1") (pin "A1") (pinfunction "A1_A1") (pintype "passive"))
      (node (ref "J1") (pin "A12") (pinfunction "A12_A12") (pintype "passive"))
      (node (ref "J1") (pin "B1") (pinfunction "B1_B1") (pintype "passive"))
      (node (ref "J1") (pin "B12") (pinfunction "B12_B12") (pintype "passive"))
      (node (ref "J2") (pin "6") (pinfunction "-_6") (pintype "passive"))
      (node (ref "J3") (pin "29") (pinfunction "-_29") (pintype "passive"))
      (node (ref "J4") (pin "2") (pinfunction "+_2") (pintype "passive"))
      (node (ref "Q2") (pin "2") (pinfunction "E_2") (pintype "passive"))
      (node (ref "R10") (pin "2") (pinfunction "2_2") (pintype "passive"))
      (node (ref "R11") (pin "2") (pinfunction "2_2") (pintype "passive"))
      (node (ref "R12") (pin "2") (pinfunction "2_2") (pintype "passive"))
      (node (ref "SW1") (pin "4") (pinfunction "4_4") (pintype "passive"))
      (node (ref "U1") (pin "8") (pinfunction "GND_8") (pintype "power_in"))
      (node (ref "U10") (pin "8") (pinfunction "GND_8") (pintype "power_in"))
      (node (ref "U11") (pin "10") (pinfunction "GND_10") (pintype "power_in"))
      (node (ref "U2") (pin "10") (pinfunction "GND_10") (pintype "power_in"))
      (node (ref "U3") (pin "16") (pinfunction "GND_16") (pintype "power_in"))
      (node (ref "U3") (pin "6") (pinfunction "GND_6") (pintype "power_in"))
      (node (ref "U4") (pin "21") (pinfunction "AGND_21") (pintype "power_in"))
      (node (ref "U4") (pin "3") (pinfunction "GND_3") (pintype "power_in"))
      (node (ref "U4") (pin "5") (pinfunction "GND_5") (pintype "power_in"))
      (node (ref "U5") (pin "2") (pinfunction "GND_2") (pintype "power_in"))
      (node (ref "U6") (pin "8") (pinfunction "GND_8") (pintype "power_in"))
      (node (ref "U7") (pin "10") (pinfunction "A16_10") (pintype "passive"))
      (node (ref "U7") (pin "24") (pinfunction "GND_24") (pintype "power_in"))
      (node (ref "U7") (pin "30") (pinfunction "~{CE1}_30") (pintype "power_in"))
      (node (ref "U8") (pin "4") (pinfunction "GND_4") (pintype "power_in"))
      (node (ref "U9") (pin "10") (pinfunction "GND_10") (pintype "power_in"))
    )
    (net (code "74") (name "Net-(D1-A-Pad3)") (class "Default")
      (node (ref "D1") (pin "3") (pinfunction "A_3") (pintype "passive"))
      (node (ref "J1") (pin "A7") (pinfunction "A7_A7") (pintype "passive"))
      (node (ref "J1") (pin "B7") (pinfunction "B7_B7") (pintype "passive"))
      (node (ref "R7") (pin "1") (pinfunction "1_1") (pintype "passive"))
    )
    (net (code "75") (name "Net-(D1-A-Pad4)") (class "Default")
      (node (ref "D1") (pin "4") (pinfunction "A_4") (pintype "passive"))
      (node (ref "J1") (pin "A6") (pinfunction "A6_A6") (pintype "passive"))
      (node (ref "J1") (pin "B6") (pinfunction "B6_B6") (pintype "passive"))
      (node (ref "R8") (pin "1") (pinfunction "1_1") (pintype "passive"))
    )
    (net (code "76") (name "Net-(D2-A)") (class "Default")
      (node (ref "D2") (pin "1") (pinfunction "A_1") (pintype "passive"))
      (node (ref "R13") (pin "2") (pinfunction "2_2") (pintype "passive"))
    )
    (net (code "77") (name "Net-(D3-A)") (class "Default")
      (node (ref "D3") (pin "1") (pinfunction "A_1") (pintype "passive"))
      (node (ref "R14") (pin "2") (pinfunction "2_2") (pintype "passive"))
    )
    (net (code "78") (name "Net-(J1-PadA5)") (class "Default")
      (node (ref "J1") (pin "A5") (pinfunction "A5_A5") (pintype "passive"))
      (node (ref "R10") (pin "1") (pinfunction "1_1") (pintype "passive"))
    )
    (net (code "79") (name "Net-(J1-PadB5)") (class "Default")
      (node (ref "J1") (pin "B5") (pinfunction "B5_B5") (pintype "passive"))
      (node (ref "R11") (pin "1") (pinfunction "1_1") (pintype "passive"))
    )
    (net (code "80") (name "Net-(Q1-B)") (class "Default")
      (node (ref "Q1") (pin "1") (pinfunction "B_1") (pintype "passive"))
      (node (ref "R4") (pin "1") (pinfunction "1_1") (pintype "passive"))
    )
    (net (code "81") (name "Net-(Q1-C)") (class "Default")
      (node (ref "Q1") (pin "3") (pinfunction "C_3") (pintype "passive"))
      (node (ref "R15") (pin "2") (pinfunction "2_2") (pintype "passive"))
    )
    (net (code "82") (name "Net-(Q2-B)") (class "Default")
      (node (ref "Q2") (pin "1") (pinfunction "B_1") (pintype "passive"))
      (node (ref "R17") (pin "1") (pinfunction "1_1") (pintype "passive"))
    )
    (net (code "83") (name "Net-(Q2-C)") (class "Default")
      (node (ref "Q2") (pin "3") (pinfunction "C_3") (pintype "passive"))
      (node (ref "R16") (pin "2") (pinfunction "2_2") (pintype "passive"))
    )
    (net (code "84") (name "Net-(U3-3V3OUT)") (class "Default")
      (node (ref "C2") (pin "1") (pinfunction "1_1") (pintype "passive"))
      (node (ref "U3") (pin "13") (pinfunction "3V3OUT_13") (pintype "power_in"))
      (node (ref "U3") (pin "14") (pinfunction "~{RESET}_14") (pintype "power_in"))
    )
    (net (code "85") (name "Net-(U3-RXD)") (class "Default")
      (node (ref "U3") (pin "4") (pinfunction "RXD_4") (pintype "power_in"))
      (node (ref "U4") (pin "31") (pinfunction "PD1/TXD_31") (pintype "passive"))
    )
    (net (code "86") (name "Net-(U3-TXD)") (class "Default")
      (node (ref "U3") (pin "20") (pinfunction "TXD_20") (pintype "power_in"))
      (node (ref "U4") (pin "30") (pinfunction "PD0/RXD_30") (pintype "passive"))
    )
    (net (code "87") (name "Net-(U3-USBDM)") (class "Default")
      (node (ref "R7") (pin "2") (pinfunction "2_2") (pintype "passive"))
      (node (ref "U3") (pin "12") (pinfunction "USBDM_12") (pintype "power_in"))
    )
    (net (code "88") (name "Net-(U3-USBDP)") (class "Default")
      (node (ref "R8") (pin "2") (pinfunction "2_2") (pintype "passive"))
      (node (ref "U3") (pin "11") (pinfunction "USBDP_11") (pintype "power_in"))
    )
    (net (code "89") (name "Net-(U3-~{DTR})") (class "Default")
      (node (ref "C1") (pin "1") (pinfunction "1_1") (pintype "passive"))
      (node (ref "U3") (pin "1") (pinfunction "~{DTR}_1") (pintype "power_in"))
    )
    (net (code "90") (name "Net-(U4-AREF)") (class "Default")
      (node (ref "C5") (pin "1") (pinfunction "1_1") (pintype "passive"))
      (node (ref "U4") (pin "20") (pinfunction "AREF_20") (pintype "power_in"))
    )
    (net (code "91") (name "Net-(U4-PB1{slash}OC1)") (class "Default")
      (node (ref "SW1") (pin "2") (pinfunction "2_2") (pintype "passive"))
      (node (ref "U4") (pin "13") (pinfunction "PB1/OC1_13") (pintype "passive"))
    )
    (net (code "92") (name "Net-(U4-PB6{slash}XTAL1)") (class "Default")
      (node (ref "C3") (pin "1") (pinfunction "1_1") (pintype "passive"))
      (node (ref "U4") (pin "7") (pinfunction "PB6/XTAL1_7") (pintype "passive"))
      (node (ref "X1") (pin "1") (pinfunction "OSC1_1") (pintype "passive"))
    )
    (net (code "93") (name "Net-(U4-PB7{slash}XTAL2)") (class "Default")
      (node (ref "C4") (pin "1") (pinfunction "1_1") (pintype "passive"))
      (node (ref "U4") (pin "8") (pinfunction "PB7/XTAL2_8") (pintype "passive"))
      (node (ref "X1") (pin "2") (pinfunction "OSC2_2") (pintype "passive"))
    )
    (net (code "94") (name "Net-(U4-PD2{slash}INT0)") (class "Default")
      (node (ref "U4") (pin "32") (pinfunction "PD2/INT0_32") (pintype "passive"))
      (node (ref "U5") (pin "1") (pinfunction "1_1") (pintype "passive"))
    )
    (net (code "95") (name "VBUS") (class "Default")
      (node (ref "J1") (pin "A4") (pinfunction "A4_A4") (pintype "passive"))
      (node (ref "J1") (pin "A9") (pinfunction "A9_A9") (pintype "passive"))
      (node (ref "J1") (pin "B4") (pinfunction "B4_B4") (pintype "passive"))
      (node (ref "J1") (pin "B9") (pinfunction "B9_B9") (pintype "passive"))
      (node (ref "R9") (pin "1") (pinfunction "1_1") (pintype "passive"))
    )
    (net (code "96") (name "VCC") (class "Default")
      (node (ref "C10") (pin "1") (pinfunction "1_1") (pintype "passive"))
      (node (ref "C11") (pin "1") (pinfunction "1_1") (pintype "passive"))
      (node (ref "C12") (pin "1") (pinfunction "1_1") (pintype "passive"))
      (node (ref "C13") (pin "1") (pinfunction "1_1") (pintype "passive"))
      (node (ref "C14") (pin "1") (pinfunction "1_1") (pintype "passive"))
      (node (ref "C15") (pin "1") (pinfunction "1_1") (pintype "passive"))
      (node (ref "C16") (pin "1") (pinfunction "1_1") (pintype "passive"))
      (node (ref "C18") (pin "1") (pinfunction "1_1") (pintype "passive"))
      (node (ref "C6") (pin "1") (pinfunction "1_1") (pintype "passive"))
      (node (ref "C7") (pin "1") (pinfunction "1_1") (pintype "passive"))
      (node (ref "C8") (pin "1") (pinfunction "1_1") (pintype "passive"))
      (node (ref "C9") (pin "1") (pinfunction "1_1") (pintype "passive"))
      (node (ref "D1") (pin "5") (pinfunction "A_5") (pintype "passive"))
      (node (ref "D2") (pin "2") (pinfunction "K_2") (pintype "passive"))
      (node (ref "D3") (pin "2") (pinfunction "K_2") (pintype "passive"))
      (node (ref "DISP1") (pin "2") (pinfunction "VCC_2") (pintype "passive"))
      (node (ref "J2") (pin "2") (pinfunction "-_2") (pintype "passive"))
      (node (ref "J3") (pin "4") (pinfunction "-_4") (pintype "passive"))
      (node (ref "Q1") (pin "2") (pinfunction "E_2") (pintype "passive"))
      (node (ref "R1") (pin "2") (pinfunction "2_2") (pintype "passive"))
      (node (ref "R2") (pin "2") (pinfunction "2_2") (pintype "passive"))
      (node (ref "R3") (pin "2") (pinfunction "2_2") (pintype "passive"))
      (node (ref "R5") (pin "2") (pinfunction "2_2") (pintype "passive"))
      (node (ref "R6") (pin "2") (pinfunction "2_2") (pintype "passive"))
      (node (ref "U1") (pin "10") (pinfunction "~{SCLR}_10") (pintype "power_in"))
      (node (ref "U1") (pin "16") (pinfunction "VCC_16") (pintype "power_in"))
      (node (ref "U10") (pin "10") (pinfunction "~{SCLR}_10") (pintype "power_in"))
      (node (ref "U10") (pin "16") (pinfunction "VCC_16") (pintype "power_in"))
      (node (ref "U11") (pin "20") (pinfunction "VCC_20") (pintype "power_in"))
      (node (ref "U2") (pin "20") (pinfunction "VCC_20") (pintype "power_in"))
      (node (ref "U3") (pin "15") (pinfunction "VCC_15") (pintype "power_in"))
      (node (ref "U3") (pin "3") (pinfunction "VCCIO_3") (pintype "power_in"))
      (node (ref "U4") (pin "18") (pinfunction "AVCC_18") (pintype "power_in"))
      (node (ref "U4") (pin "4") (pinfunction "VCC_4") (pintype "power_in"))
      (node (ref "U4") (pin "6") (pinfunction "VCC_6") (pintype "power_in"))
      (node (ref "U5") (pin "5") (pinfunction "VCC_5") (pintype "power_in"))
      (node (ref "U6") (pin "10") (pinfunction "~{SCLR}_10") (pintype "power_in"))
      (node (ref "U6") (pin "16") (pinfunction "VCC_16") (pintype "power_in"))
      (node (ref "U7") (pin "6") (pinfunction "CE2_6") (pintype "power_in"))
      (node (ref "U7") (pin "8") (pinfunction "VCC_8") (pintype "power_in"))
      (node (ref "U8") (pin "3") (pinfunction "~{WP}_3") (pintype "input"))
      (node (ref "U8") (pin "7") (pinfunction "~{HOLD}_7") (pintype "input"))
      (node (ref "U8") (pin "8") (pinfunction "VCC_8") (pintype "power_in"))
      (node (ref "U9") (pin "20") (pinfunction "VCC_20") (pintype "power_in"))
    )
    (net (code "97") (name "unconnected-(J1-PadA8)") (class "Default")
      (node (ref "J1") (pin "A8") (pinfunction "A8_A8") (pintype "passive"))
    )
    (net (code "98") (name "unconnected-(J1-PadB8)") (class "Default")
      (node (ref "J1") (pin "B8") (pinfunction "B8_B8") (pintype "passive"))
    )
    (net (code "99") (name "unconnected-(SW1-Pad1)") (class "Default")
      (node (ref "SW1") (pin "1") (pinfunction "1_1") (pintype "passive"))
    )
    (net (code "100") (name "unconnected-(SW1-Pad3)") (class "Default")
      (node (ref "SW1") (pin "3") (pinfunction "3_3") (pintype "passive"))
    )
    (net (code "101") (name "unconnected-(U1-QH'-Pad9)") (class "Default")
      (node (ref "U1") (pin "9") (pinfunction "QH'_9") (pintype "power_in"))
    )
    (net (code "102") (name "unconnected-(U3-CBUS0-Pad18)") (class "Default")
      (node (ref "U3") (pin "18") (pinfunction "CBUS0_18") (pintype "power_in"))
    )
    (net (code "103") (name "unconnected-(U3-CBUS1-Pad17)") (class "Default")
      (node (ref "U3") (pin "17") (pinfunction "CBUS1_17") (pintype "power_in"))
    )
    (net (code "104") (name "unconnected-(U3-~{CTS}-Pad9)") (class "Default")
      (node (ref "U3") (pin "9") (pinfunction "~{CTS}_9") (pintype "power_in"))
    )
    (net (code "105") (name "unconnected-(U3-~{DCD}-Pad8)") (class "Default")
      (node (ref "U3") (pin "8") (pinfunction "~{DCD}_8") (pintype "power_in"))
    )
    (net (code "106") (name "unconnected-(U3-~{DSR}-Pad7)") (class "Default")
      (node (ref "U3") (pin "7") (pinfunction "~{DSR}_7") (pintype "power_in"))
    )
    (net (code "107") (name "unconnected-(U3-~{RI}-Pad5)") (class "Default")
      (node (ref "U3") (pin "5") (pinfunction "~{RI}_5") (pintype "power_in"))
    )
    (net (code "108") (name "unconnected-(U3-~{RTS}-Pad2)") (class "Default")
      (node (ref "U3") (pin "2") (pinfunction "~{RTS}_2") (pintype "power_in"))
    )
    (net (code "109") (name "unconnected-(U4-ADC6-Pad19)") (class "Default")
      (node (ref "U4") (pin "19") (pinfunction "ADC6_19") (pintype "passive"))
    )
    (net (code "110") (name "unconnected-(U6-QH'-Pad9)") (class "Default")
      (node (ref "U6") (pin "9") (pinfunction "QH'_9") (pintype "power_in"))
    )
    (net (code "111") (name "unconnected-(U10-QH'-Pad9)") (class "Default")
      (node (ref "U10") (pin "9") (pinfunction "QH'_9") (pintype "power_in"))
    )
  )
)
